# C64_SVideo_Cable_Pro.net
KiCad netlist of a schematic drawn in EAGLE
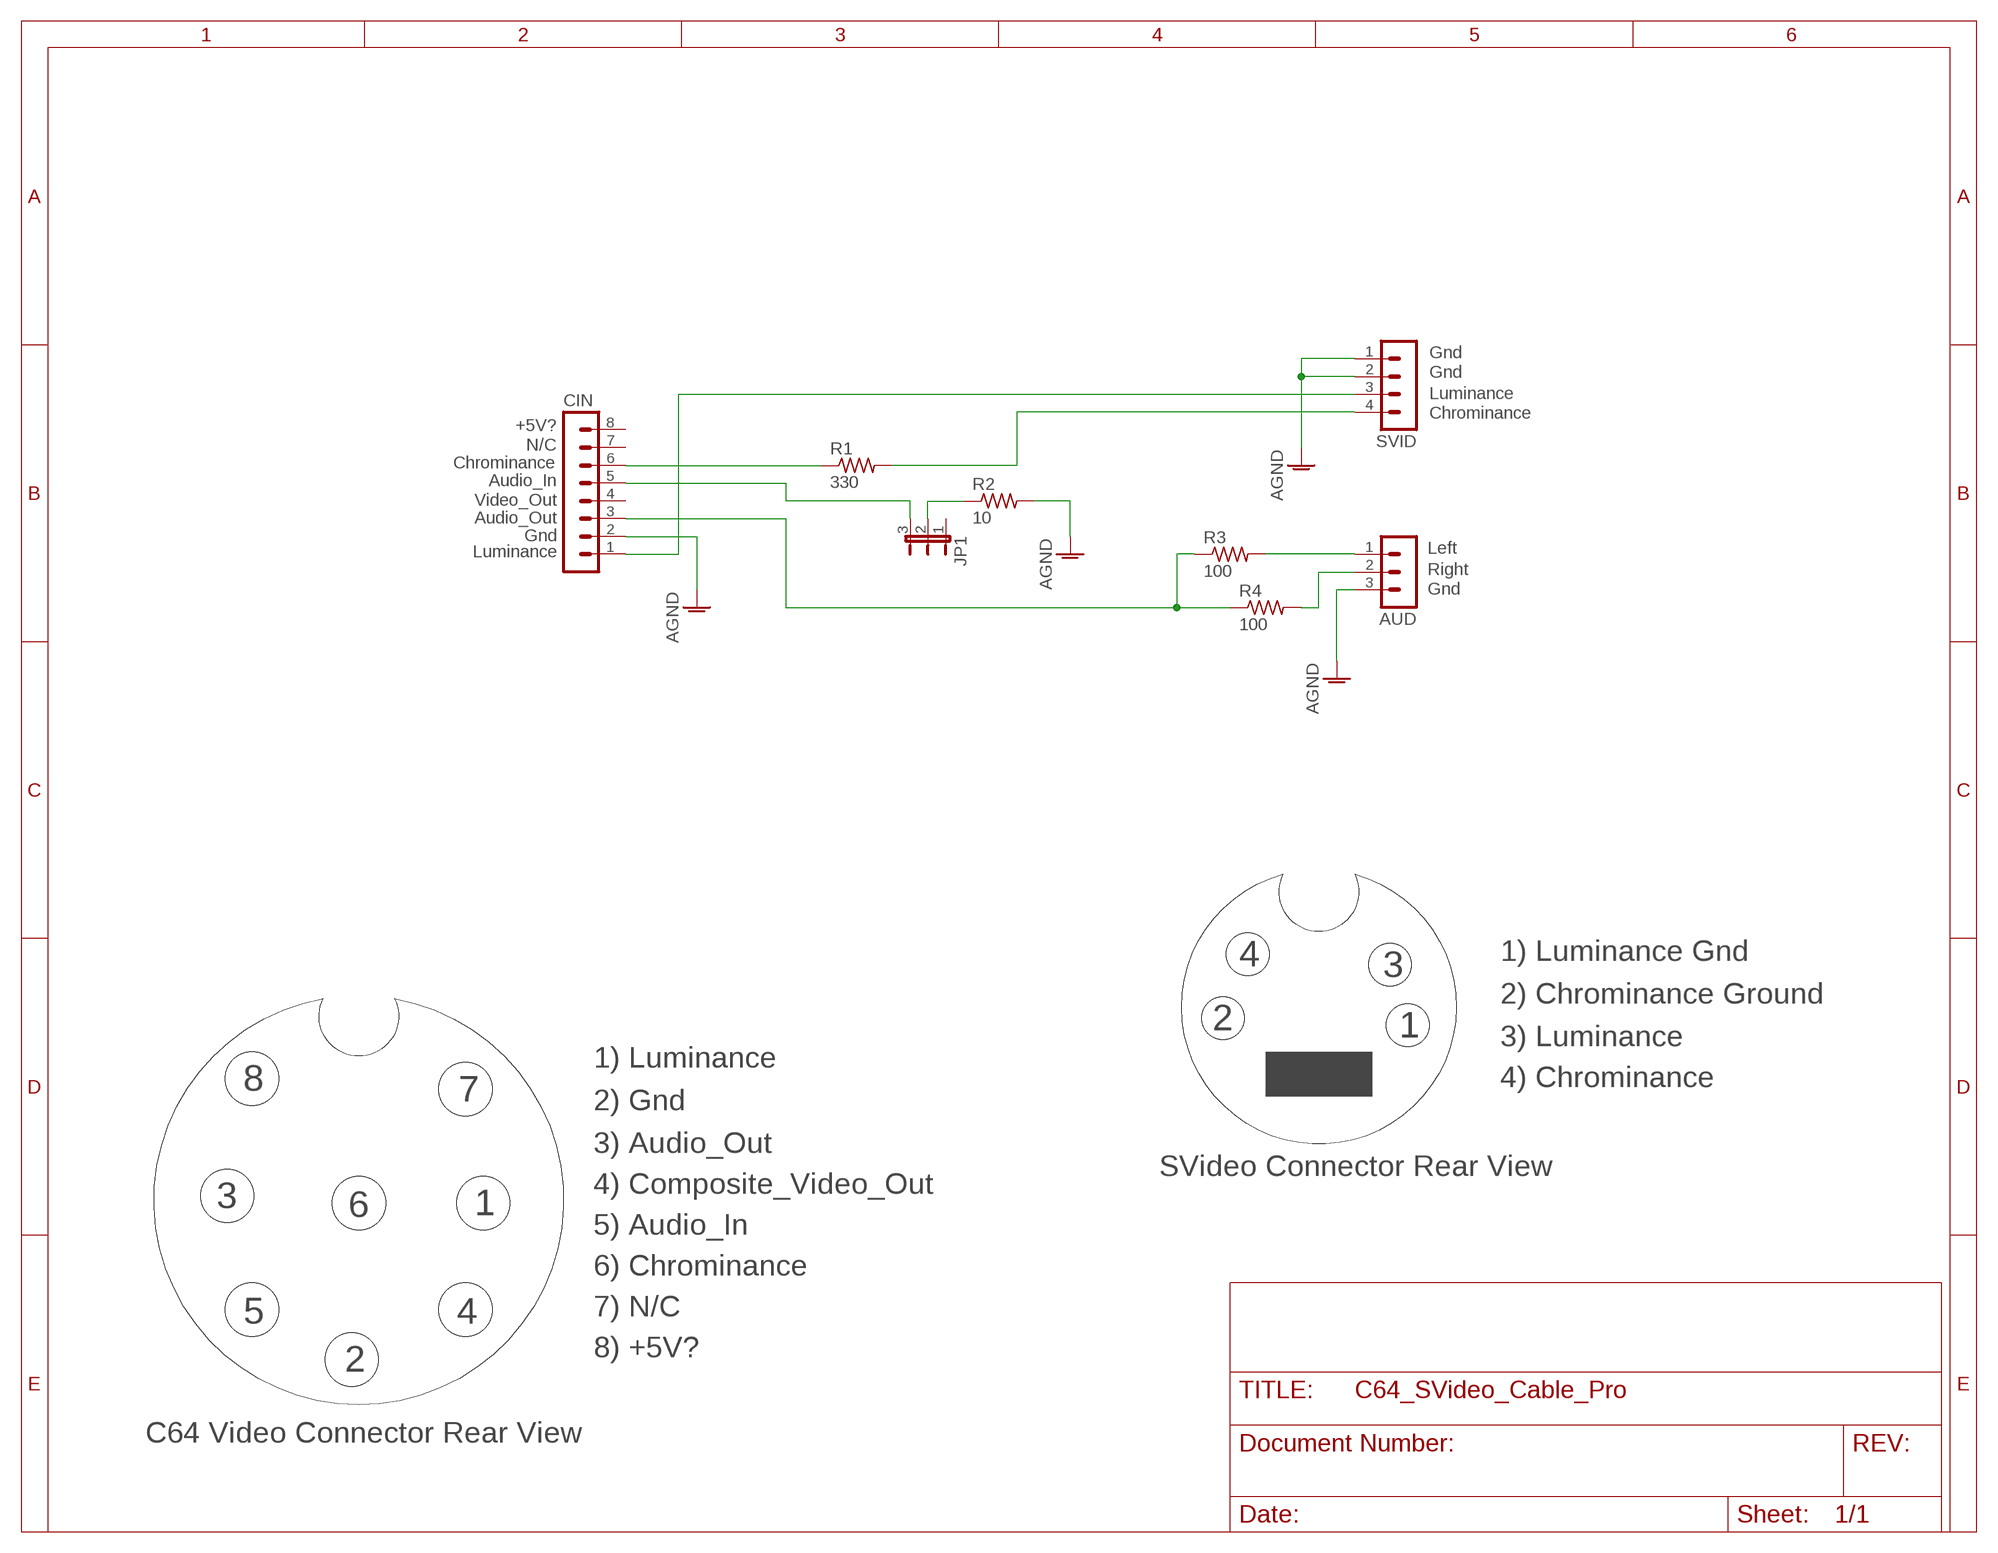
[diagram p0: schematic, sheet 1]

(export (version "E")
  (design (tool "Eeschema 10.0.6"))
  (components
    (comp (ref "AUD")
      (value "MA03-1")
      (footprint "eagle-import:MA03-1")
      (libsource (lib "eagle-import") (part "MA03-1"))
    )
    (comp (ref "CIN")
      (value "MA08-1")
      (footprint "eagle-import:MA08-1")
      (libsource (lib "eagle-import") (part "MA08-1"))
    )
    (comp (ref "JP1")
      (value "JP2E")
      (footprint "eagle-import:JP2")
      (libsource (lib "eagle-import") (part "JP2E"))
    )
    (comp (ref "R1")
      (value "330")
      (footprint "eagle-import:0309_12")
      (libsource (lib "eagle-import") (part "R-US_0309/12"))
    )
    (comp (ref "R2")
      (value "10")
      (footprint "eagle-import:0309_12")
      (libsource (lib "eagle-import") (part "R-US_0309/12"))
    )
    (comp (ref "R3")
      (value "100")
      (footprint "eagle-import:0309_12")
      (libsource (lib "eagle-import") (part "R-US_0309/12"))
    )
    (comp (ref "R4")
      (value "100")
      (footprint "eagle-import:0309_12")
      (libsource (lib "eagle-import") (part "R-US_0309/12"))
    )
    (comp (ref "SVID")
      (value "MA04-1")
      (footprint "eagle-import:MA04-1")
      (libsource (lib "eagle-import") (part "MA04-1"))
    )
  )
  (nets
    (net (code "1") (name "AGND") (class "Default")
      (node (ref "AUD") (pin "3") (pinfunction "3_3") (pintype "passive"))
      (node (ref "CIN") (pin "2") (pinfunction "2_2") (pintype "passive"))
      (node (ref "R2") (pin "2") (pinfunction "2_2") (pintype "passive"))
      (node (ref "SVID") (pin "1") (pinfunction "1_1") (pintype "passive"))
      (node (ref "SVID") (pin "2") (pinfunction "2_2") (pintype "passive"))
    )
    (net (code "2") (name "Net-(AUD-Pad1)") (class "Default")
      (node (ref "AUD") (pin "1") (pinfunction "1_1") (pintype "passive"))
      (node (ref "R3") (pin "2") (pinfunction "2_2") (pintype "passive"))
    )
    (net (code "3") (name "Net-(AUD-Pad2)") (class "Default")
      (node (ref "AUD") (pin "2") (pinfunction "2_2") (pintype "passive"))
      (node (ref "R4") (pin "2") (pinfunction "2_2") (pintype "passive"))
    )
    (net (code "4") (name "Net-(CIN-Pad1)") (class "Default")
      (node (ref "CIN") (pin "1") (pinfunction "1_1") (pintype "passive"))
      (node (ref "SVID") (pin "3") (pinfunction "3_3") (pintype "passive"))
    )
    (net (code "5") (name "Net-(CIN-Pad3)") (class "Default")
      (node (ref "CIN") (pin "3") (pinfunction "3_3") (pintype "passive"))
      (node (ref "R3") (pin "1") (pinfunction "1_1") (pintype "passive"))
      (node (ref "R4") (pin "1") (pinfunction "1_1") (pintype "passive"))
    )
    (net (code "6") (name "Net-(CIN-Pad5)") (class "Default")
      (node (ref "CIN") (pin "5") (pinfunction "5_5") (pintype "passive"))
      (node (ref "JP1") (pin "3") (pinfunction "3_3") (pintype "passive"))
    )
    (net (code "7") (name "Net-(CIN-Pad6)") (class "Default")
      (node (ref "CIN") (pin "6") (pinfunction "6_6") (pintype "passive"))
      (node (ref "R1") (pin "1") (pinfunction "1_1") (pintype "passive"))
    )
    (net (code "8") (name "Net-(JP1-Pad2)") (class "Default")
      (node (ref "JP1") (pin "2") (pinfunction "2_2") (pintype "passive"))
      (node (ref "R2") (pin "1") (pinfunction "1_1") (pintype "passive"))
    )
    (net (code "9") (name "Net-(R1-Pad2)") (class "Default")
      (node (ref "R1") (pin "2") (pinfunction "2_2") (pintype "passive"))
      (node (ref "SVID") (pin "4") (pinfunction "4_4") (pintype "passive"))
    )
    (net (code "10") (name "unconnected-(CIN-Pad4)") (class "Default")
      (node (ref "CIN") (pin "4") (pinfunction "4_4") (pintype "passive"))
    )
    (net (code "11") (name "unconnected-(CIN-Pad7)") (class "Default")
      (node (ref "CIN") (pin "7") (pinfunction "7_7") (pintype "passive"))
    )
    (net (code "12") (name "unconnected-(CIN-Pad8)") (class "Default")
      (node (ref "CIN") (pin "8") (pinfunction "8_8") (pintype "passive"))
    )
    (net (code "13") (name "unconnected-(JP1-Pad1)") (class "Default")
      (node (ref "JP1") (pin "1") (pinfunction "1_1") (pintype "passive"))
    )
  )
)
